# untitled.net
KiCad netlist of a schematic drawn in EAGLE
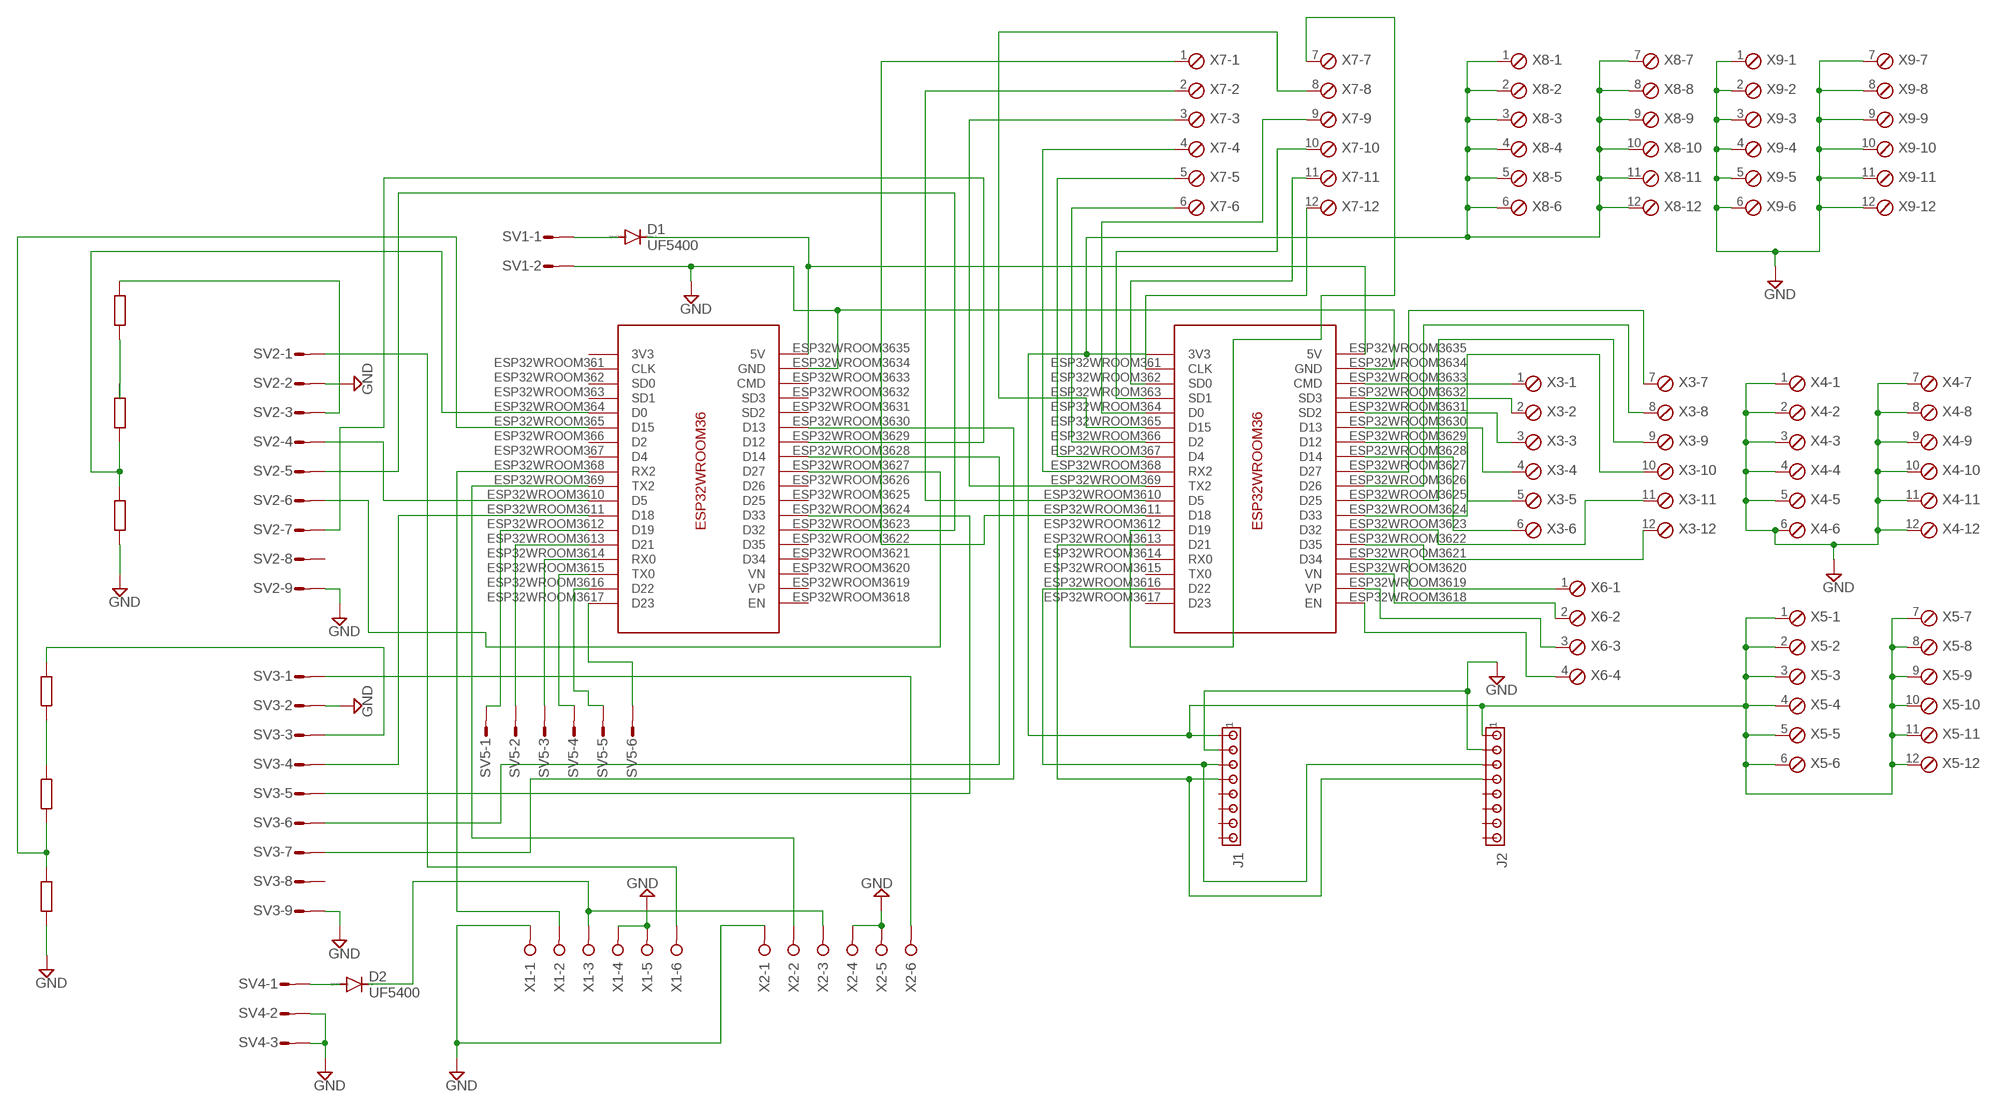
[diagram p0: schematic, sheet 1]

(export (version "E")
  (design (tool "Eeschema 10.0.6"))
  (components
    (comp (ref "D1")
      (value "UF5400")
      (footprint "eagle-import:DO201-15")
      (libsource (lib "eagle-import") (part "UF5400"))
    )
    (comp (ref "D2")
      (value "UF5400")
      (footprint "eagle-import:DO201-15")
      (libsource (lib "eagle-import") (part "UF5400"))
    )
    (comp (ref "J1")
      (value "MTA08-100")
      (footprint "eagle-import:10X08MTA")
      (libsource (lib "eagle-import") (part "MTA08-100"))
    )
    (comp (ref "J2")
      (value "MTA08-100")
      (footprint "eagle-import:10X08MTA")
      (libsource (lib "eagle-import") (part "MTA08-100"))
    )
    (comp (ref "SV1")
      (value "L02P")
      (footprint "eagle-import:L02P")
      (libsource (lib "eagle-import") (part "L02P"))
    )
    (comp (ref "SV2")
      (value "L09P")
      (footprint "eagle-import:L09P")
      (libsource (lib "eagle-import") (part "L09P"))
    )
    (comp (ref "SV3")
      (value "L09P")
      (footprint "eagle-import:L09P")
      (libsource (lib "eagle-import") (part "L09P"))
    )
    (comp (ref "SV4")
      (value "L03P")
      (footprint "eagle-import:L03P")
      (libsource (lib "eagle-import") (part "L03P"))
    )
    (comp (ref "SV5")
      (value "L06P")
      (footprint "eagle-import:L06P")
      (libsource (lib "eagle-import") (part "L06P"))
    )
    (comp (ref "U$1")
      (value "ESP32WROOM36")
      (footprint "eagle-import:ESP32WROOM36PINDIP")
      (libsource (lib "eagle-import") (part "ESP32WROOM36"))
    )
    (comp (ref "U$2")
      (value "ESP32WROOM36")
      (footprint "eagle-import:ESP32WROOM36PINDIP")
      (libsource (lib "eagle-import") (part "ESP32WROOM36"))
    )
    (comp (ref "X1")
      (value "W237-06P")
      (footprint "eagle-import:W237-6P")
      (libsource (lib "eagle-import") (part "W237-06P"))
    )
    (comp (ref "X2")
      (value "W237-06P")
      (footprint "eagle-import:W237-6P")
      (libsource (lib "eagle-import") (part "W237-06P"))
    )
    (comp (ref "X3")
      (value "MPT12")
      (footprint "eagle-import:12POL254")
      (libsource (lib "eagle-import") (part "MPT12"))
    )
    (comp (ref "X4")
      (value "MPT12")
      (footprint "eagle-import:12POL254")
      (libsource (lib "eagle-import") (part "MPT12"))
    )
    (comp (ref "X5")
      (value "MPT12")
      (footprint "eagle-import:12POL254")
      (libsource (lib "eagle-import") (part "MPT12"))
    )
    (comp (ref "X6")
      (value "MPT4")
      (footprint "eagle-import:4POL254")
      (libsource (lib "eagle-import") (part "MPT4"))
    )
    (comp (ref "X7")
      (value "MPT12")
      (footprint "eagle-import:12POL254")
      (libsource (lib "eagle-import") (part "MPT12"))
    )
    (comp (ref "X8")
      (value "MPT12")
      (footprint "eagle-import:12POL254")
      (libsource (lib "eagle-import") (part "MPT12"))
    )
    (comp (ref "X9")
      (value "MPT12")
      (footprint "eagle-import:12POL254")
      (libsource (lib "eagle-import") (part "MPT12"))
    )
  )
  (nets
    (net (code "1") (name "GND") (class "Default")
      (node (ref "J1") (pin "2") (pinfunction "2_2") (pintype "passive"))
      (node (ref "J2") (pin "2") (pinfunction "2_2") (pintype "passive"))
      (node (ref "SV1") (pin "2") (pinfunction "S_2") (pintype "passive"))
      (node (ref "SV2") (pin "2") (pinfunction "S_2") (pintype "passive"))
      (node (ref "SV2") (pin "9") (pinfunction "S_9") (pintype "passive"))
      (node (ref "SV3") (pin "2") (pinfunction "S_2") (pintype "passive"))
      (node (ref "SV3") (pin "9") (pinfunction "S_9") (pintype "passive"))
      (node (ref "SV4") (pin "2") (pinfunction "S_2") (pintype "passive"))
      (node (ref "SV4") (pin "3") (pinfunction "S_3") (pintype "passive"))
      (node (ref "U$1") (pin "ESP32WROOM3634") (pinfunction "GND_ESP32WROOM3634") (pintype "bidirectional"))
      (node (ref "U$2") (pin "ESP32WROOM3634") (pinfunction "GND_ESP32WROOM3634") (pintype "bidirectional"))
      (node (ref "X1") (pin "1") (pinfunction "KL_1") (pintype "passive"))
      (node (ref "X1") (pin "4") (pinfunction "KL_4") (pintype "passive"))
      (node (ref "X1") (pin "5") (pinfunction "KL_5") (pintype "passive"))
      (node (ref "X2") (pin "1") (pinfunction "KL_1") (pintype "passive"))
      (node (ref "X2") (pin "4") (pinfunction "KL_4") (pintype "passive"))
      (node (ref "X2") (pin "5") (pinfunction "KL_5") (pintype "passive"))
      (node (ref "X4") (pin "1") (pinfunction "1_1") (pintype "passive"))
      (node (ref "X4") (pin "10") (pinfunction "1_10") (pintype "passive"))
      (node (ref "X4") (pin "11") (pinfunction "1_11") (pintype "passive"))
      (node (ref "X4") (pin "12") (pinfunction "1_12") (pintype "passive"))
      (node (ref "X4") (pin "2") (pinfunction "1_2") (pintype "passive"))
      (node (ref "X4") (pin "3") (pinfunction "1_3") (pintype "passive"))
      (node (ref "X4") (pin "4") (pinfunction "1_4") (pintype "passive"))
      (node (ref "X4") (pin "5") (pinfunction "1_5") (pintype "passive"))
      (node (ref "X4") (pin "6") (pinfunction "1_6") (pintype "passive"))
      (node (ref "X4") (pin "7") (pinfunction "1_7") (pintype "passive"))
      (node (ref "X4") (pin "8") (pinfunction "1_8") (pintype "passive"))
      (node (ref "X4") (pin "9") (pinfunction "1_9") (pintype "passive"))
      (node (ref "X9") (pin "1") (pinfunction "1_1") (pintype "passive"))
      (node (ref "X9") (pin "10") (pinfunction "1_10") (pintype "passive"))
      (node (ref "X9") (pin "11") (pinfunction "1_11") (pintype "passive"))
      (node (ref "X9") (pin "12") (pinfunction "1_12") (pintype "passive"))
      (node (ref "X9") (pin "2") (pinfunction "1_2") (pintype "passive"))
      (node (ref "X9") (pin "3") (pinfunction "1_3") (pintype "passive"))
      (node (ref "X9") (pin "4") (pinfunction "1_4") (pintype "passive"))
      (node (ref "X9") (pin "5") (pinfunction "1_5") (pintype "passive"))
      (node (ref "X9") (pin "6") (pinfunction "1_6") (pintype "passive"))
      (node (ref "X9") (pin "7") (pinfunction "1_7") (pintype "passive"))
      (node (ref "X9") (pin "8") (pinfunction "1_8") (pintype "passive"))
      (node (ref "X9") (pin "9") (pinfunction "1_9") (pintype "passive"))
    )
    (net (code "2") (name "Net-(SV1A-S)") (class "Default")
      (node (ref "D1") (pin "A") (pinfunction "A_A") (pintype "passive"))
      (node (ref "SV1") (pin "1") (pinfunction "S_1") (pintype "passive"))
    )
    (net (code "3") (name "Net-(SV2A-S)") (class "Default")
      (node (ref "SV2") (pin "1") (pinfunction "S_1") (pintype "passive"))
      (node (ref "X1") (pin "6") (pinfunction "KL_6") (pintype "passive"))
    )
    (net (code "4") (name "Net-(SV2D-S)") (class "Default")
      (node (ref "SV2") (pin "4") (pinfunction "S_4") (pintype "passive"))
      (node (ref "U$1") (pin "ESP32WROOM3610") (pinfunction "D5_ESP32WROOM3610") (pintype "bidirectional"))
    )
    (net (code "5") (name "Net-(SV2E-S)") (class "Default")
      (node (ref "SV2") (pin "5") (pinfunction "S_5") (pintype "passive"))
      (node (ref "U$1") (pin "ESP32WROOM3623") (pinfunction "D32_ESP32WROOM3623") (pintype "bidirectional"))
    )
    (net (code "6") (name "Net-(SV2F-S)") (class "Default")
      (node (ref "SV2") (pin "6") (pinfunction "S_6") (pintype "passive"))
      (node (ref "U$1") (pin "ESP32WROOM3627") (pinfunction "D27_ESP32WROOM3627") (pintype "bidirectional"))
    )
    (net (code "7") (name "Net-(SV2G-S)") (class "Default")
      (node (ref "SV2") (pin "7") (pinfunction "S_7") (pintype "passive"))
      (node (ref "U$1") (pin "ESP32WROOM3629") (pinfunction "D12_ESP32WROOM3629") (pintype "bidirectional"))
    )
    (net (code "8") (name "Net-(SV3A-S)") (class "Default")
      (node (ref "SV3") (pin "1") (pinfunction "S_1") (pintype "passive"))
      (node (ref "X2") (pin "6") (pinfunction "KL_6") (pintype "passive"))
    )
    (net (code "9") (name "Net-(SV3D-S)") (class "Default")
      (node (ref "SV3") (pin "4") (pinfunction "S_4") (pintype "passive"))
      (node (ref "U$1") (pin "ESP32WROOM3611") (pinfunction "D18_ESP32WROOM3611") (pintype "bidirectional"))
    )
    (net (code "10") (name "Net-(SV3E-S)") (class "Default")
      (node (ref "SV3") (pin "5") (pinfunction "S_5") (pintype "passive"))
      (node (ref "U$1") (pin "ESP32WROOM3624") (pinfunction "D33_ESP32WROOM3624") (pintype "bidirectional"))
    )
    (net (code "11") (name "Net-(SV3F-S)") (class "Default")
      (node (ref "SV3") (pin "6") (pinfunction "S_6") (pintype "passive"))
      (node (ref "U$1") (pin "ESP32WROOM3628") (pinfunction "D14_ESP32WROOM3628") (pintype "bidirectional"))
    )
    (net (code "12") (name "Net-(SV3G-S)") (class "Default")
      (node (ref "SV3") (pin "7") (pinfunction "S_7") (pintype "passive"))
      (node (ref "U$1") (pin "ESP32WROOM3630") (pinfunction "D13_ESP32WROOM3630") (pintype "bidirectional"))
    )
    (net (code "13") (name "Net-(SV4A-S)") (class "Default")
      (node (ref "D2") (pin "A") (pinfunction "A_A") (pintype "passive"))
      (node (ref "SV4") (pin "1") (pinfunction "S_1") (pintype "passive"))
    )
    (net (code "14") (name "Net-(SV5A-S)") (class "Default")
      (node (ref "SV5") (pin "1") (pinfunction "S_1") (pintype "passive"))
      (node (ref "U$1") (pin "ESP32WROOM3612") (pinfunction "D19_ESP32WROOM3612") (pintype "bidirectional"))
    )
    (net (code "15") (name "Net-(SV5B-S)") (class "Default")
      (node (ref "SV5") (pin "2") (pinfunction "S_2") (pintype "passive"))
      (node (ref "U$1") (pin "ESP32WROOM3613") (pinfunction "D21_ESP32WROOM3613") (pintype "bidirectional"))
    )
    (net (code "16") (name "Net-(SV5C-S)") (class "Default")
      (node (ref "SV5") (pin "3") (pinfunction "S_3") (pintype "passive"))
      (node (ref "U$1") (pin "ESP32WROOM3614") (pinfunction "RX0_ESP32WROOM3614") (pintype "bidirectional"))
    )
    (net (code "17") (name "Net-(SV5D-S)") (class "Default")
      (node (ref "SV5") (pin "4") (pinfunction "S_4") (pintype "passive"))
      (node (ref "U$1") (pin "ESP32WROOM3615") (pinfunction "TX0_ESP32WROOM3615") (pintype "bidirectional"))
    )
    (net (code "18") (name "Net-(SV5E-S)") (class "Default")
      (node (ref "SV5") (pin "5") (pinfunction "S_5") (pintype "passive"))
      (node (ref "U$1") (pin "ESP32WROOM3616") (pinfunction "D22_ESP32WROOM3616") (pintype "bidirectional"))
    )
    (net (code "19") (name "Net-(SV5F-S)") (class "Default")
      (node (ref "SV5") (pin "6") (pinfunction "S_6") (pintype "passive"))
      (node (ref "U$1") (pin "ESP32WROOM3617") (pinfunction "D23_ESP32WROOM3617") (pintype "bidirectional"))
    )
    (net (code "20") (name "Net-(U$1-5V)") (class "Default")
      (node (ref "D1") (pin "C") (pinfunction "C_C") (pintype "passive"))
      (node (ref "U$1") (pin "ESP32WROOM3635") (pinfunction "5V_ESP32WROOM3635") (pintype "bidirectional"))
      (node (ref "U$2") (pin "ESP32WROOM3635") (pinfunction "5V_ESP32WROOM3635") (pintype "bidirectional"))
    )
    (net (code "21") (name "Net-(U$1-RX2)") (class "Default")
      (node (ref "U$1") (pin "ESP32WROOM368") (pinfunction "RX2_ESP32WROOM368") (pintype "bidirectional"))
      (node (ref "X1") (pin "2") (pinfunction "KL_2") (pintype "passive"))
    )
    (net (code "22") (name "Net-(U$1-TX2)") (class "Default")
      (node (ref "U$1") (pin "ESP32WROOM369") (pinfunction "TX2_ESP32WROOM369") (pintype "bidirectional"))
      (node (ref "X2") (pin "2") (pinfunction "KL_2") (pintype "passive"))
    )
    (net (code "23") (name "Net-(U$2-3V3)") (class "Default")
      (node (ref "J1") (pin "1") (pinfunction "1_1") (pintype "passive"))
      (node (ref "J2") (pin "1") (pinfunction "1_1") (pintype "passive"))
      (node (ref "U$2") (pin "ESP32WROOM360") (pinfunction "3V3_ESP32WROOM360") (pintype "bidirectional"))
      (node (ref "X5") (pin "1") (pinfunction "1_1") (pintype "passive"))
      (node (ref "X5") (pin "10") (pinfunction "1_10") (pintype "passive"))
      (node (ref "X5") (pin "11") (pinfunction "1_11") (pintype "passive"))
      (node (ref "X5") (pin "12") (pinfunction "1_12") (pintype "passive"))
      (node (ref "X5") (pin "2") (pinfunction "1_2") (pintype "passive"))
      (node (ref "X5") (pin "3") (pinfunction "1_3") (pintype "passive"))
      (node (ref "X5") (pin "4") (pinfunction "1_4") (pintype "passive"))
      (node (ref "X5") (pin "5") (pinfunction "1_5") (pintype "passive"))
      (node (ref "X5") (pin "6") (pinfunction "1_6") (pintype "passive"))
      (node (ref "X5") (pin "7") (pinfunction "1_7") (pintype "passive"))
      (node (ref "X5") (pin "8") (pinfunction "1_8") (pintype "passive"))
      (node (ref "X5") (pin "9") (pinfunction "1_9") (pintype "passive"))
      (node (ref "X8") (pin "1") (pinfunction "1_1") (pintype "passive"))
      (node (ref "X8") (pin "10") (pinfunction "1_10") (pintype "passive"))
      (node (ref "X8") (pin "11") (pinfunction "1_11") (pintype "passive"))
      (node (ref "X8") (pin "12") (pinfunction "1_12") (pintype "passive"))
      (node (ref "X8") (pin "2") (pinfunction "1_2") (pintype "passive"))
      (node (ref "X8") (pin "3") (pinfunction "1_3") (pintype "passive"))
      (node (ref "X8") (pin "4") (pinfunction "1_4") (pintype "passive"))
      (node (ref "X8") (pin "5") (pinfunction "1_5") (pintype "passive"))
      (node (ref "X8") (pin "6") (pinfunction "1_6") (pintype "passive"))
      (node (ref "X8") (pin "7") (pinfunction "1_7") (pintype "passive"))
      (node (ref "X8") (pin "8") (pinfunction "1_8") (pintype "passive"))
      (node (ref "X8") (pin "9") (pinfunction "1_9") (pintype "passive"))
    )
    (net (code "24") (name "Net-(U$2-CLK)") (class "Default")
      (node (ref "U$2") (pin "ESP32WROOM361") (pinfunction "CLK_ESP32WROOM361") (pintype "bidirectional"))
      (node (ref "X7") (pin "12") (pinfunction "1_12") (pintype "passive"))
    )
    (net (code "25") (name "Net-(U$2-CMD)") (class "Default")
      (node (ref "U$2") (pin "ESP32WROOM3633") (pinfunction "CMD_ESP32WROOM3633") (pintype "bidirectional"))
      (node (ref "X3") (pin "1") (pinfunction "1_1") (pintype "passive"))
    )
    (net (code "26") (name "Net-(U$2-D0)") (class "Default")
      (node (ref "U$2") (pin "ESP32WROOM364") (pinfunction "D0_ESP32WROOM364") (pintype "bidirectional"))
      (node (ref "X7") (pin "9") (pinfunction "1_9") (pintype "passive"))
    )
    (net (code "27") (name "Net-(U$2-D2)") (class "Default")
      (node (ref "U$2") (pin "ESP32WROOM366") (pinfunction "D2_ESP32WROOM366") (pintype "bidirectional"))
      (node (ref "X7") (pin "6") (pinfunction "1_6") (pintype "passive"))
    )
    (net (code "28") (name "Net-(U$2-D4)") (class "Default")
      (node (ref "U$2") (pin "ESP32WROOM367") (pinfunction "D4_ESP32WROOM367") (pintype "bidirectional"))
      (node (ref "X7") (pin "5") (pinfunction "1_5") (pintype "passive"))
    )
    (net (code "29") (name "Net-(U$2-D5)") (class "Default")
      (node (ref "U$2") (pin "ESP32WROOM3610") (pinfunction "D5_ESP32WROOM3610") (pintype "bidirectional"))
      (node (ref "X7") (pin "2") (pinfunction "1_2") (pintype "passive"))
    )
    (net (code "30") (name "Net-(U$2-D12)") (class "Default")
      (node (ref "U$2") (pin "ESP32WROOM3629") (pinfunction "D12_ESP32WROOM3629") (pintype "bidirectional"))
      (node (ref "X3") (pin "5") (pinfunction "1_5") (pintype "passive"))
    )
    (net (code "31") (name "Net-(U$2-D13)") (class "Default")
      (node (ref "U$2") (pin "ESP32WROOM3630") (pinfunction "D13_ESP32WROOM3630") (pintype "bidirectional"))
      (node (ref "X3") (pin "4") (pinfunction "1_4") (pintype "passive"))
    )
    (net (code "32") (name "Net-(U$2-D14)") (class "Default")
      (node (ref "U$2") (pin "ESP32WROOM3628") (pinfunction "D14_ESP32WROOM3628") (pintype "bidirectional"))
      (node (ref "X3") (pin "6") (pinfunction "1_6") (pintype "passive"))
    )
    (net (code "33") (name "Net-(U$2-D15)") (class "Default")
      (node (ref "U$2") (pin "ESP32WROOM365") (pinfunction "D15_ESP32WROOM365") (pintype "bidirectional"))
      (node (ref "X7") (pin "8") (pinfunction "1_8") (pintype "passive"))
    )
    (net (code "34") (name "Net-(U$2-D18)") (class "Default")
      (node (ref "U$2") (pin "ESP32WROOM3611") (pinfunction "D18_ESP32WROOM3611") (pintype "bidirectional"))
      (node (ref "X7") (pin "1") (pinfunction "1_1") (pintype "passive"))
    )
    (net (code "35") (name "Net-(U$2-D19)") (class "Default")
      (node (ref "U$2") (pin "ESP32WROOM3612") (pinfunction "D19_ESP32WROOM3612") (pintype "bidirectional"))
      (node (ref "X7") (pin "7") (pinfunction "1_7") (pintype "passive"))
    )
    (net (code "36") (name "Net-(U$2-D21)") (class "Default")
      (node (ref "J1") (pin "4") (pinfunction "4_4") (pintype "passive"))
      (node (ref "J2") (pin "4") (pinfunction "4_4") (pintype "passive"))
      (node (ref "U$2") (pin "ESP32WROOM3613") (pinfunction "D21_ESP32WROOM3613") (pintype "bidirectional"))
    )
    (net (code "37") (name "Net-(U$2-D22)") (class "Default")
      (node (ref "J1") (pin "3") (pinfunction "3_3") (pintype "passive"))
      (node (ref "J2") (pin "3") (pinfunction "3_3") (pintype "passive"))
      (node (ref "U$2") (pin "ESP32WROOM3616") (pinfunction "D22_ESP32WROOM3616") (pintype "bidirectional"))
    )
    (net (code "38") (name "Net-(U$2-D25)") (class "Default")
      (node (ref "U$2") (pin "ESP32WROOM3625") (pinfunction "D25_ESP32WROOM3625") (pintype "bidirectional"))
      (node (ref "X3") (pin "9") (pinfunction "1_9") (pintype "passive"))
    )
    (net (code "39") (name "Net-(U$2-D26)") (class "Default")
      (node (ref "U$2") (pin "ESP32WROOM3626") (pinfunction "D26_ESP32WROOM3626") (pintype "bidirectional"))
      (node (ref "X3") (pin "8") (pinfunction "1_8") (pintype "passive"))
    )
    (net (code "40") (name "Net-(U$2-D27)") (class "Default")
      (node (ref "U$2") (pin "ESP32WROOM3627") (pinfunction "D27_ESP32WROOM3627") (pintype "bidirectional"))
      (node (ref "X3") (pin "7") (pinfunction "1_7") (pintype "passive"))
    )
    (net (code "41") (name "Net-(U$2-D32)") (class "Default")
      (node (ref "U$2") (pin "ESP32WROOM3623") (pinfunction "D32_ESP32WROOM3623") (pintype "bidirectional"))
      (node (ref "X3") (pin "11") (pinfunction "1_11") (pintype "passive"))
    )
    (net (code "42") (name "Net-(U$2-D33)") (class "Default")
      (node (ref "U$2") (pin "ESP32WROOM3624") (pinfunction "D33_ESP32WROOM3624") (pintype "bidirectional"))
      (node (ref "X3") (pin "10") (pinfunction "1_10") (pintype "passive"))
    )
    (net (code "43") (name "Net-(U$2-D34)") (class "Default")
      (node (ref "U$2") (pin "ESP32WROOM3621") (pinfunction "D34_ESP32WROOM3621") (pintype "bidirectional"))
      (node (ref "X6") (pin "1") (pinfunction "1_1") (pintype "passive"))
    )
    (net (code "44") (name "Net-(U$2-D35)") (class "Default")
      (node (ref "U$2") (pin "ESP32WROOM3622") (pinfunction "D35_ESP32WROOM3622") (pintype "bidirectional"))
      (node (ref "X3") (pin "12") (pinfunction "1_12") (pintype "passive"))
    )
    (net (code "45") (name "Net-(U$2-EN)") (class "Default")
      (node (ref "U$2") (pin "ESP32WROOM3618") (pinfunction "EN_ESP32WROOM3618") (pintype "bidirectional"))
      (node (ref "X6") (pin "4") (pinfunction "1_4") (pintype "passive"))
    )
    (net (code "46") (name "Net-(U$2-RX2)") (class "Default")
      (node (ref "U$2") (pin "ESP32WROOM368") (pinfunction "RX2_ESP32WROOM368") (pintype "bidirectional"))
      (node (ref "X7") (pin "4") (pinfunction "1_4") (pintype "passive"))
    )
    (net (code "47") (name "Net-(U$2-SD0)") (class "Default")
      (node (ref "U$2") (pin "ESP32WROOM362") (pinfunction "SD0_ESP32WROOM362") (pintype "bidirectional"))
      (node (ref "X7") (pin "11") (pinfunction "1_11") (pintype "passive"))
    )
    (net (code "48") (name "Net-(U$2-SD1)") (class "Default")
      (node (ref "U$2") (pin "ESP32WROOM363") (pinfunction "SD1_ESP32WROOM363") (pintype "bidirectional"))
      (node (ref "X7") (pin "10") (pinfunction "1_10") (pintype "passive"))
    )
    (net (code "49") (name "Net-(U$2-SD2)") (class "Default")
      (node (ref "U$2") (pin "ESP32WROOM3631") (pinfunction "SD2_ESP32WROOM3631") (pintype "bidirectional"))
      (node (ref "X3") (pin "3") (pinfunction "1_3") (pintype "passive"))
    )
    (net (code "50") (name "Net-(U$2-SD3)") (class "Default")
      (node (ref "U$2") (pin "ESP32WROOM3632") (pinfunction "SD3_ESP32WROOM3632") (pintype "bidirectional"))
      (node (ref "X3") (pin "2") (pinfunction "1_2") (pintype "passive"))
    )
    (net (code "51") (name "Net-(U$2-TX2)") (class "Default")
      (node (ref "U$2") (pin "ESP32WROOM369") (pinfunction "TX2_ESP32WROOM369") (pintype "bidirectional"))
      (node (ref "X7") (pin "3") (pinfunction "1_3") (pintype "passive"))
    )
    (net (code "52") (name "Net-(U$2-VN)") (class "Default")
      (node (ref "U$2") (pin "ESP32WROOM3620") (pinfunction "VN_ESP32WROOM3620") (pintype "bidirectional"))
      (node (ref "X6") (pin "2") (pinfunction "1_2") (pintype "passive"))
    )
    (net (code "53") (name "Net-(U$2-VP)") (class "Default")
      (node (ref "U$2") (pin "ESP32WROOM3619") (pinfunction "VP_ESP32WROOM3619") (pintype "bidirectional"))
      (node (ref "X6") (pin "3") (pinfunction "1_3") (pintype "passive"))
    )
    (net (code "54") (name "Net-(X1C-KL)") (class "Default")
      (node (ref "D2") (pin "C") (pinfunction "C_C") (pintype "passive"))
      (node (ref "X1") (pin "3") (pinfunction "KL_3") (pintype "passive"))
      (node (ref "X2") (pin "3") (pinfunction "KL_3") (pintype "passive"))
    )
    (net (code "55") (name "unconnected-(J1-Pad5)") (class "Default")
      (node (ref "J1") (pin "5") (pinfunction "5_5") (pintype "passive"))
    )
    (net (code "56") (name "unconnected-(J1-Pad6)") (class "Default")
      (node (ref "J1") (pin "6") (pinfunction "6_6") (pintype "passive"))
    )
    (net (code "57") (name "unconnected-(J1-Pad7)") (class "Default")
      (node (ref "J1") (pin "7") (pinfunction "7_7") (pintype "passive"))
    )
    (net (code "58") (name "unconnected-(J1-Pad8)") (class "Default")
      (node (ref "J1") (pin "8") (pinfunction "8_8") (pintype "passive"))
    )
    (net (code "59") (name "unconnected-(J2-Pad5)") (class "Default")
      (node (ref "J2") (pin "5") (pinfunction "5_5") (pintype "passive"))
    )
    (net (code "60") (name "unconnected-(J2-Pad6)") (class "Default")
      (node (ref "J2") (pin "6") (pinfunction "6_6") (pintype "passive"))
    )
    (net (code "61") (name "unconnected-(J2-Pad7)") (class "Default")
      (node (ref "J2") (pin "7") (pinfunction "7_7") (pintype "passive"))
    )
    (net (code "62") (name "unconnected-(J2-Pad8)") (class "Default")
      (node (ref "J2") (pin "8") (pinfunction "8_8") (pintype "passive"))
    )
    (net (code "63") (name "unconnected-(SV2C-S-Pad3)") (class "Default")
      (node (ref "SV2") (pin "3") (pinfunction "S_3") (pintype "passive"))
    )
    (net (code "64") (name "unconnected-(SV2H-S-Pad8)") (class "Default")
      (node (ref "SV2") (pin "8") (pinfunction "S_8") (pintype "passive"))
    )
    (net (code "65") (name "unconnected-(SV3C-S-Pad3)") (class "Default")
      (node (ref "SV3") (pin "3") (pinfunction "S_3") (pintype "passive"))
    )
    (net (code "66") (name "unconnected-(SV3H-S-Pad8)") (class "Default")
      (node (ref "SV3") (pin "8") (pinfunction "S_8") (pintype "passive"))
    )
    (net (code "67") (name "unconnected-(U$1-3V3-PadESP32WROOM360)") (class "Default")
      (node (ref "U$1") (pin "ESP32WROOM360") (pinfunction "3V3_ESP32WROOM360") (pintype "bidirectional"))
    )
    (net (code "68") (name "unconnected-(U$1-CLK-PadESP32WROOM361)") (class "Default")
      (node (ref "U$1") (pin "ESP32WROOM361") (pinfunction "CLK_ESP32WROOM361") (pintype "bidirectional"))
    )
    (net (code "69") (name "unconnected-(U$1-CMD-PadESP32WROOM3633)") (class "Default")
      (node (ref "U$1") (pin "ESP32WROOM3633") (pinfunction "CMD_ESP32WROOM3633") (pintype "bidirectional"))
    )
    (net (code "70") (name "unconnected-(U$1-D0-PadESP32WROOM364)") (class "Default")
      (node (ref "U$1") (pin "ESP32WROOM364") (pinfunction "D0_ESP32WROOM364") (pintype "bidirectional"))
    )
    (net (code "71") (name "unconnected-(U$1-D2-PadESP32WROOM366)") (class "Default")
      (node (ref "U$1") (pin "ESP32WROOM366") (pinfunction "D2_ESP32WROOM366") (pintype "bidirectional"))
    )
    (net (code "72") (name "unconnected-(U$1-D4-PadESP32WROOM367)") (class "Default")
      (node (ref "U$1") (pin "ESP32WROOM367") (pinfunction "D4_ESP32WROOM367") (pintype "bidirectional"))
    )
    (net (code "73") (name "unconnected-(U$1-D15-PadESP32WROOM365)") (class "Default")
      (node (ref "U$1") (pin "ESP32WROOM365") (pinfunction "D15_ESP32WROOM365") (pintype "bidirectional"))
    )
    (net (code "74") (name "unconnected-(U$1-D25-PadESP32WROOM3625)") (class "Default")
      (node (ref "U$1") (pin "ESP32WROOM3625") (pinfunction "D25_ESP32WROOM3625") (pintype "bidirectional"))
    )
    (net (code "75") (name "unconnected-(U$1-D26-PadESP32WROOM3626)") (class "Default")
      (node (ref "U$1") (pin "ESP32WROOM3626") (pinfunction "D26_ESP32WROOM3626") (pintype "bidirectional"))
    )
    (net (code "76") (name "unconnected-(U$1-D34-PadESP32WROOM3621)") (class "Default")
      (node (ref "U$1") (pin "ESP32WROOM3621") (pinfunction "D34_ESP32WROOM3621") (pintype "bidirectional"))
    )
    (net (code "77") (name "unconnected-(U$1-D35-PadESP32WROOM3622)") (class "Default")
      (node (ref "U$1") (pin "ESP32WROOM3622") (pinfunction "D35_ESP32WROOM3622") (pintype "bidirectional"))
    )
    (net (code "78") (name "unconnected-(U$1-EN-PadESP32WROOM3618)") (class "Default")
      (node (ref "U$1") (pin "ESP32WROOM3618") (pinfunction "EN_ESP32WROOM3618") (pintype "bidirectional"))
    )
    (net (code "79") (name "unconnected-(U$1-SD0-PadESP32WROOM362)") (class "Default")
      (node (ref "U$1") (pin "ESP32WROOM362") (pinfunction "SD0_ESP32WROOM362") (pintype "bidirectional"))
    )
    (net (code "80") (name "unconnected-(U$1-SD1-PadESP32WROOM363)") (class "Default")
      (node (ref "U$1") (pin "ESP32WROOM363") (pinfunction "SD1_ESP32WROOM363") (pintype "bidirectional"))
    )
    (net (code "81") (name "unconnected-(U$1-SD2-PadESP32WROOM3631)") (class "Default")
      (node (ref "U$1") (pin "ESP32WROOM3631") (pinfunction "SD2_ESP32WROOM3631") (pintype "bidirectional"))
    )
    (net (code "82") (name "unconnected-(U$1-SD3-PadESP32WROOM3632)") (class "Default")
      (node (ref "U$1") (pin "ESP32WROOM3632") (pinfunction "SD3_ESP32WROOM3632") (pintype "bidirectional"))
    )
    (net (code "83") (name "unconnected-(U$1-VN-PadESP32WROOM3620)") (class "Default")
      (node (ref "U$1") (pin "ESP32WROOM3620") (pinfunction "VN_ESP32WROOM3620") (pintype "bidirectional"))
    )
    (net (code "84") (name "unconnected-(U$1-VP-PadESP32WROOM3619)") (class "Default")
      (node (ref "U$1") (pin "ESP32WROOM3619") (pinfunction "VP_ESP32WROOM3619") (pintype "bidirectional"))
    )
    (net (code "85") (name "unconnected-(U$2-D23-PadESP32WROOM3617)") (class "Default")
      (node (ref "U$2") (pin "ESP32WROOM3617") (pinfunction "D23_ESP32WROOM3617") (pintype "bidirectional"))
    )
    (net (code "86") (name "unconnected-(U$2-RX0-PadESP32WROOM3614)") (class "Default")
      (node (ref "U$2") (pin "ESP32WROOM3614") (pinfunction "RX0_ESP32WROOM3614") (pintype "bidirectional"))
    )
    (net (code "87") (name "unconnected-(U$2-TX0-PadESP32WROOM3615)") (class "Default")
      (node (ref "U$2") (pin "ESP32WROOM3615") (pinfunction "TX0_ESP32WROOM3615") (pintype "bidirectional"))
    )
  )
)
